# PANS.net
KiCad netlist of a schematic drawn in EAGLE
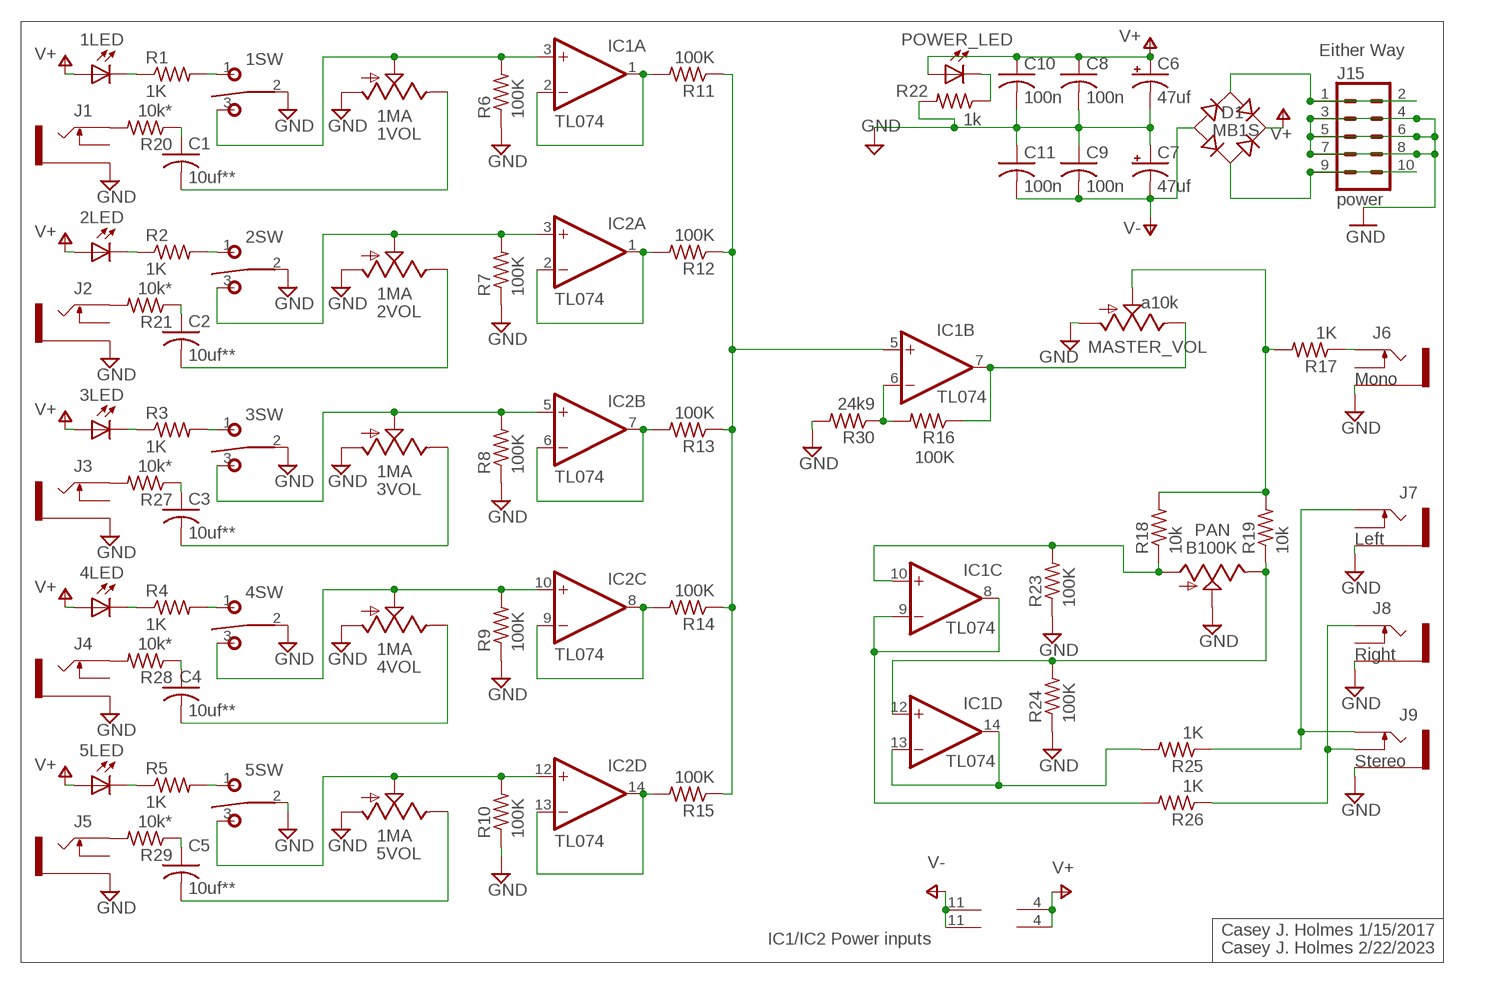
[diagram p0: schematic, sheet 1]

(export (version "E")
  (design (tool "Eeschema 10.0.6"))
  (components
    (comp (ref "1LED")
      (value "green")
      (footprint "eagle-import:LED5MM")
      (libsource (lib "eagle-import") (part "LED5MM"))
    )
    (comp (ref "1SW")
      (value "on/on")
      (footprint "eagle-import:M9040P")
      (libsource (lib "eagle-import") (part "T-80-T-SPDT-ON-OFF-ON"))
    )
    (comp (ref "1VOL")
      (value "1MA")
      (footprint "eagle-import:9MM_SNAP-IN_POT")
      (libsource (lib "eagle-import") (part "9MM_SNAP-IN_POT_"))
    )
    (comp (ref "2LED")
      (value "green")
      (footprint "eagle-import:LED5MM")
      (libsource (lib "eagle-import") (part "LED5MM"))
    )
    (comp (ref "2SW")
      (value "on/on")
      (footprint "eagle-import:M9040P")
      (libsource (lib "eagle-import") (part "T-80-T-SPDT-ON-OFF-ON"))
    )
    (comp (ref "2VOL")
      (value "1MA")
      (footprint "eagle-import:9MM_SNAP-IN_POT")
      (libsource (lib "eagle-import") (part "9MM_SNAP-IN_POT_"))
    )
    (comp (ref "3LED")
      (value "green")
      (footprint "eagle-import:LED5MM")
      (libsource (lib "eagle-import") (part "LED5MM"))
    )
    (comp (ref "3SW")
      (value "on/on")
      (footprint "eagle-import:M9040P")
      (libsource (lib "eagle-import") (part "T-80-T-SPDT-ON-OFF-ON"))
    )
    (comp (ref "3VOL")
      (value "1MA")
      (footprint "eagle-import:9MM_SNAP-IN_POT")
      (libsource (lib "eagle-import") (part "9MM_SNAP-IN_POT_"))
    )
    (comp (ref "4LED")
      (value "green")
      (footprint "eagle-import:LED5MM")
      (libsource (lib "eagle-import") (part "LED5MM"))
    )
    (comp (ref "4SW")
      (value "on/on")
      (footprint "eagle-import:M9040P")
      (libsource (lib "eagle-import") (part "T-80-T-SPDT-ON-OFF-ON"))
    )
    (comp (ref "4VOL")
      (value "1MA")
      (footprint "eagle-import:9MM_SNAP-IN_POT")
      (libsource (lib "eagle-import") (part "9MM_SNAP-IN_POT_"))
    )
    (comp (ref "5LED")
      (value "green")
      (footprint "eagle-import:LED5MM")
      (libsource (lib "eagle-import") (part "LED5MM"))
    )
    (comp (ref "5SW")
      (value "on/on")
      (footprint "eagle-import:M9040P")
      (libsource (lib "eagle-import") (part "T-80-T-SPDT-ON-OFF-ON"))
    )
    (comp (ref "5VOL")
      (value "1MA")
      (footprint "eagle-import:9MM_SNAP-IN_POT")
      (libsource (lib "eagle-import") (part "9MM_SNAP-IN_POT_"))
    )
    (comp (ref "C1")
      (value "10uf**")
      (footprint "eagle-import:C0805K")
      (libsource (lib "eagle-import") (part "C-USC0805K"))
    )
    (comp (ref "C2")
      (value "10uf**")
      (footprint "eagle-import:C0805K")
      (libsource (lib "eagle-import") (part "C-USC0805K"))
    )
    (comp (ref "C3")
      (value "10uf**")
      (footprint "eagle-import:C0805K")
      (libsource (lib "eagle-import") (part "C-USC0805K"))
    )
    (comp (ref "C4")
      (value "10uf**")
      (footprint "eagle-import:C0805K")
      (libsource (lib "eagle-import") (part "C-USC0805K"))
    )
    (comp (ref "C5")
      (value "10uf**")
      (footprint "eagle-import:C0805K")
      (libsource (lib "eagle-import") (part "C-USC0805K"))
    )
    (comp (ref "C6")
      (value "47uf")
      (footprint "eagle-import:PANASONIC_D")
      (libsource (lib "eagle-import") (part "CPOL-USD"))
    )
    (comp (ref "C7")
      (value "47uf")
      (footprint "eagle-import:PANASONIC_D")
      (libsource (lib "eagle-import") (part "CPOL-USD"))
    )
    (comp (ref "C8")
      (value "100n")
      (footprint "eagle-import:C0805")
      (libsource (lib "eagle-import") (part "resistor_C-USC0805"))
    )
    (comp (ref "C9")
      (value "100n")
      (footprint "eagle-import:C0805")
      (libsource (lib "eagle-import") (part "resistor_C-USC0805"))
    )
    (comp (ref "C10")
      (value "100n")
      (footprint "eagle-import:C0805")
      (libsource (lib "eagle-import") (part "resistor_C-USC0805"))
    )
    (comp (ref "C11")
      (value "100n")
      (footprint "eagle-import:C0805")
      (libsource (lib "eagle-import") (part "resistor_C-USC0805"))
    )
    (comp (ref "D1")
      (value "MB1S")
      (footprint "eagle-import:SOIC-4")
      (libsource (lib "eagle-import") (part "MBS1"))
    )
    (comp (ref "IC1")
      (value "TL074")
      (footprint "eagle-import:SO14")
      (libsource (lib "eagle-import") (part "TL074_SMD"))
    )
    (comp (ref "IC2")
      (value "TL074")
      (footprint "eagle-import:SO14")
      (libsource (lib "eagle-import") (part "TL074_SMD"))
    )
    (comp (ref "J1")
      (value "THONKICONNNEW")
      (footprint "eagle-import:WQP-PJ301M-12_JACK")
      (libsource (lib "eagle-import") (part "THONKICONNNEW"))
    )
    (comp (ref "J2")
      (value "THONKICONNNEW")
      (footprint "eagle-import:WQP-PJ301M-12_JACK")
      (libsource (lib "eagle-import") (part "THONKICONNNEW"))
    )
    (comp (ref "J3")
      (value "THONKICONNNEW")
      (footprint "eagle-import:WQP-PJ301M-12_JACK")
      (libsource (lib "eagle-import") (part "THONKICONNNEW"))
    )
    (comp (ref "J4")
      (value "THONKICONNNEW")
      (footprint "eagle-import:WQP-PJ301M-12_JACK")
      (libsource (lib "eagle-import") (part "THONKICONNNEW"))
    )
    (comp (ref "J5")
      (value "THONKICONNNEW")
      (footprint "eagle-import:WQP-PJ301M-12_JACK")
      (libsource (lib "eagle-import") (part "THONKICONNNEW"))
    )
    (comp (ref "J6")
      (value "THONKICONNNEW")
      (footprint "eagle-import:WQP-PJ301M-12_JACK")
      (libsource (lib "eagle-import") (part "THONKICONNNEW"))
    )
    (comp (ref "J7")
      (value "LEFT")
      (footprint "eagle-import:WQP-PJ301M-12_JACK")
      (libsource (lib "eagle-import") (part "THONKICONNNEW"))
    )
    (comp (ref "J8")
      (value "THONKICONNNEW")
      (footprint "eagle-import:WQP-PJ301M-12_JACK")
      (libsource (lib "eagle-import") (part "THONKICONNNEW"))
    )
    (comp (ref "J9")
      (value "Stereo")
      (footprint "eagle-import:WQP-PJ301M-12_JACK")
      (libsource (lib "eagle-import") (part "THONKICONNNEW"))
    )
    (comp (ref "J15")
      (value "power")
      (footprint "eagle-import:2X5")
      (libsource (lib "eagle-import") (part "CONN_05X2PTH"))
    )
    (comp (ref "MASTER_VOL")
      (value "a10k")
      (footprint "eagle-import:9MM_SNAP-IN_POT")
      (libsource (lib "eagle-import") (part "9MM_SNAP-IN_POT_"))
    )
    (comp (ref "PAN")
      (value "B100K")
      (footprint "eagle-import:9MM_SNAP-IN_POT")
      (libsource (lib "eagle-import") (part "9MM_SNAP-IN_POT_"))
    )
    (comp (ref "POWER_LED")
      (value "green")
      (footprint "eagle-import:LED5MM")
      (libsource (lib "eagle-import") (part "LED5MM"))
    )
    (comp (ref "R1")
      (value "1K")
      (footprint "eagle-import:M0805")
      (libsource (lib "eagle-import") (part "R-US_M0805"))
    )
    (comp (ref "R2")
      (value "1K")
      (footprint "eagle-import:M0805")
      (libsource (lib "eagle-import") (part "R-US_M0805"))
    )
    (comp (ref "R3")
      (value "1K")
      (footprint "eagle-import:M0805")
      (libsource (lib "eagle-import") (part "R-US_M0805"))
    )
    (comp (ref "R4")
      (value "1K")
      (footprint "eagle-import:M0805")
      (libsource (lib "eagle-import") (part "R-US_M0805"))
    )
    (comp (ref "R5")
      (value "1K")
      (footprint "eagle-import:M0805")
      (libsource (lib "eagle-import") (part "R-US_M0805"))
    )
    (comp (ref "R6")
      (value "100K")
      (footprint "eagle-import:M0805")
      (libsource (lib "eagle-import") (part "R-US_M0805"))
    )
    (comp (ref "R7")
      (value "100K")
      (footprint "eagle-import:M0805")
      (libsource (lib "eagle-import") (part "R-US_M0805"))
    )
    (comp (ref "R8")
      (value "100K")
      (footprint "eagle-import:M0805")
      (libsource (lib "eagle-import") (part "R-US_M0805"))
    )
    (comp (ref "R9")
      (value "100K")
      (footprint "eagle-import:M0805")
      (libsource (lib "eagle-import") (part "R-US_M0805"))
    )
    (comp (ref "R10")
      (value "100K")
      (footprint "eagle-import:M0805")
      (libsource (lib "eagle-import") (part "R-US_M0805"))
    )
    (comp (ref "R11")
      (value "100K")
      (footprint "eagle-import:M0805")
      (libsource (lib "eagle-import") (part "R-US_M0805"))
    )
    (comp (ref "R12")
      (value "100K")
      (footprint "eagle-import:M0805")
      (libsource (lib "eagle-import") (part "R-US_M0805"))
    )
    (comp (ref "R13")
      (value "100K")
      (footprint "eagle-import:M0805")
      (libsource (lib "eagle-import") (part "R-US_M0805"))
    )
    (comp (ref "R14")
      (value "100K")
      (footprint "eagle-import:M0805")
      (libsource (lib "eagle-import") (part "R-US_M0805"))
    )
    (comp (ref "R15")
      (value "100K")
      (footprint "eagle-import:M0805")
      (libsource (lib "eagle-import") (part "R-US_M0805"))
    )
    (comp (ref "R16")
      (value "100K")
      (footprint "eagle-import:M0805")
      (libsource (lib "eagle-import") (part "R-US_M0805"))
    )
    (comp (ref "R17")
      (value "1K")
      (footprint "eagle-import:M0805")
      (libsource (lib "eagle-import") (part "R-US_M0805"))
    )
    (comp (ref "R18")
      (value "10k")
      (footprint "eagle-import:M0805")
      (libsource (lib "eagle-import") (part "R-US_M0805"))
    )
    (comp (ref "R19")
      (value "10k")
      (footprint "eagle-import:M0805")
      (libsource (lib "eagle-import") (part "R-US_M0805"))
    )
    (comp (ref "R20")
      (value "10k*")
      (footprint "eagle-import:M0805")
      (libsource (lib "eagle-import") (part "R-US_M0805"))
    )
    (comp (ref "R21")
      (value "10k*")
      (footprint "eagle-import:M0805")
      (libsource (lib "eagle-import") (part "R-US_M0805"))
    )
    (comp (ref "R22")
      (value "1k")
      (footprint "eagle-import:M0805")
      (libsource (lib "eagle-import") (part "R-US_M0805"))
    )
    (comp (ref "R23")
      (value "100K")
      (footprint "eagle-import:M0805")
      (libsource (lib "eagle-import") (part "R-US_M0805"))
    )
    (comp (ref "R24")
      (value "100K")
      (footprint "eagle-import:M0805")
      (libsource (lib "eagle-import") (part "R-US_M0805"))
    )
    (comp (ref "R25")
      (value "1K")
      (footprint "eagle-import:M0805")
      (libsource (lib "eagle-import") (part "R-US_M0805"))
    )
    (comp (ref "R26")
      (value "1K")
      (footprint "eagle-import:M0805")
      (libsource (lib "eagle-import") (part "R-US_M0805"))
    )
    (comp (ref "R27")
      (value "10k*")
      (footprint "eagle-import:M0805")
      (libsource (lib "eagle-import") (part "R-US_M0805"))
    )
    (comp (ref "R28")
      (value "10k*")
      (footprint "eagle-import:M0805")
      (libsource (lib "eagle-import") (part "R-US_M0805"))
    )
    (comp (ref "R29")
      (value "10k*")
      (footprint "eagle-import:M0805")
      (libsource (lib "eagle-import") (part "R-US_M0805"))
    )
    (comp (ref "R30")
      (value "24k9")
      (footprint "eagle-import:M0805")
      (libsource (lib "eagle-import") (part "R-US_M0805"))
    )
  )
  (nets
    (net (code "1") (name "GND") (class "Default")
      (node (ref "1SW") (pin "2") (pinfunction "P_2") (pintype "passive"))
      (node (ref "1VOL") (pin "1") (pinfunction "A_1") (pintype "passive"))
      (node (ref "2SW") (pin "2") (pinfunction "P_2") (pintype "passive"))
      (node (ref "2VOL") (pin "1") (pinfunction "A_1") (pintype "passive"))
      (node (ref "3SW") (pin "2") (pinfunction "P_2") (pintype "passive"))
      (node (ref "3VOL") (pin "1") (pinfunction "A_1") (pintype "passive"))
      (node (ref "4SW") (pin "2") (pinfunction "P_2") (pintype "passive"))
      (node (ref "4VOL") (pin "1") (pinfunction "A_1") (pintype "passive"))
      (node (ref "5SW") (pin "2") (pinfunction "P_2") (pintype "passive"))
      (node (ref "5VOL") (pin "1") (pinfunction "A_1") (pintype "passive"))
      (node (ref "C10") (pin "2") (pinfunction "2_2") (pintype "passive"))
      (node (ref "C11") (pin "1") (pinfunction "1_1") (pintype "passive"))
      (node (ref "C6") (pin "-") (pinfunction "-_-") (pintype "passive"))
      (node (ref "C7") (pin "+") (pinfunction "+_+") (pintype "passive"))
      (node (ref "C8") (pin "2") (pinfunction "2_2") (pintype "passive"))
      (node (ref "C9") (pin "1") (pinfunction "1_1") (pintype "passive"))
      (node (ref "J1") (pin "P$3_SLEEVE") (pinfunction "SLEEVE_P$3_SLEEVE") (pintype "passive"))
      (node (ref "J15") (pin "3") (pinfunction "3_3") (pintype "passive"))
      (node (ref "J15") (pin "4") (pinfunction "4_4") (pintype "passive"))
      (node (ref "J15") (pin "5") (pinfunction "5_5") (pintype "passive"))
      (node (ref "J15") (pin "6") (pinfunction "6_6") (pintype "passive"))
      (node (ref "J15") (pin "7") (pinfunction "7_7") (pintype "passive"))
      (node (ref "J15") (pin "8") (pinfunction "8_8") (pintype "passive"))
      (node (ref "J2") (pin "P$3_SLEEVE") (pinfunction "SLEEVE_P$3_SLEEVE") (pintype "passive"))
      (node (ref "J3") (pin "P$3_SLEEVE") (pinfunction "SLEEVE_P$3_SLEEVE") (pintype "passive"))
      (node (ref "J4") (pin "P$3_SLEEVE") (pinfunction "SLEEVE_P$3_SLEEVE") (pintype "passive"))
      (node (ref "J5") (pin "P$3_SLEEVE") (pinfunction "SLEEVE_P$3_SLEEVE") (pintype "passive"))
      (node (ref "J6") (pin "P$3_SLEEVE") (pinfunction "SLEEVE_P$3_SLEEVE") (pintype "passive"))
      (node (ref "J7") (pin "P$3_SLEEVE") (pinfunction "SLEEVE_P$3_SLEEVE") (pintype "passive"))
      (node (ref "J8") (pin "P$3_SLEEVE") (pinfunction "SLEEVE_P$3_SLEEVE") (pintype "passive"))
      (node (ref "J9") (pin "P$3_SLEEVE") (pinfunction "SLEEVE_P$3_SLEEVE") (pintype "passive"))
      (node (ref "MASTER_VOL") (pin "1") (pinfunction "A_1") (pintype "passive"))
      (node (ref "PAN") (pin "2") (pinfunction "S_2") (pintype "passive"))
      (node (ref "R10") (pin "1") (pinfunction "1_1") (pintype "passive"))
      (node (ref "R22") (pin "2") (pinfunction "2_2") (pintype "passive"))
      (node (ref "R23") (pin "1") (pinfunction "1_1") (pintype "passive"))
      (node (ref "R24") (pin "1") (pinfunction "1_1") (pintype "passive"))
      (node (ref "R30") (pin "2") (pinfunction "2_2") (pintype "passive"))
      (node (ref "R6") (pin "1") (pinfunction "1_1") (pintype "passive"))
      (node (ref "R7") (pin "1") (pinfunction "1_1") (pintype "passive"))
      (node (ref "R8") (pin "1") (pinfunction "1_1") (pintype "passive"))
      (node (ref "R9") (pin "1") (pinfunction "1_1") (pintype "passive"))
    )
    (net (code "2") (name "Net-(1LED-C)") (class "Default")
      (node (ref "1LED") (pin "K") (pinfunction "C_K") (pintype "passive"))
      (node (ref "R1") (pin "1") (pinfunction "1_1") (pintype "passive"))
    )
    (net (code "3") (name "Net-(1SW-O)") (class "Default")
      (node (ref "1SW") (pin "1") (pinfunction "O_1") (pintype "passive"))
      (node (ref "R1") (pin "2") (pinfunction "2_2") (pintype "passive"))
    )
    (net (code "4") (name "Net-(1SW-S)") (class "Default")
      (node (ref "1SW") (pin "3") (pinfunction "S_3") (pintype "passive"))
      (node (ref "1VOL") (pin "2") (pinfunction "S_2") (pintype "passive"))
      (node (ref "IC1") (pin "3") (pinfunction "+IN_3") (pintype "input"))
      (node (ref "R6") (pin "2") (pinfunction "2_2") (pintype "passive"))
    )
    (net (code "5") (name "Net-(1VOL-E)") (class "Default")
      (node (ref "1VOL") (pin "3") (pinfunction "E_3") (pintype "passive"))
      (node (ref "C1") (pin "2") (pinfunction "2_2") (pintype "passive"))
    )
    (net (code "6") (name "Net-(2LED-C)") (class "Default")
      (node (ref "2LED") (pin "K") (pinfunction "C_K") (pintype "passive"))
      (node (ref "R2") (pin "1") (pinfunction "1_1") (pintype "passive"))
    )
    (net (code "7") (name "Net-(2SW-O)") (class "Default")
      (node (ref "2SW") (pin "1") (pinfunction "O_1") (pintype "passive"))
      (node (ref "R2") (pin "2") (pinfunction "2_2") (pintype "passive"))
    )
    (net (code "8") (name "Net-(2SW-S)") (class "Default")
      (node (ref "2SW") (pin "3") (pinfunction "S_3") (pintype "passive"))
      (node (ref "2VOL") (pin "2") (pinfunction "S_2") (pintype "passive"))
      (node (ref "IC2") (pin "3") (pinfunction "+IN_3") (pintype "input"))
      (node (ref "R7") (pin "2") (pinfunction "2_2") (pintype "passive"))
    )
    (net (code "9") (name "Net-(2VOL-E)") (class "Default")
      (node (ref "2VOL") (pin "3") (pinfunction "E_3") (pintype "passive"))
      (node (ref "C2") (pin "2") (pinfunction "2_2") (pintype "passive"))
    )
    (net (code "10") (name "Net-(3LED-C)") (class "Default")
      (node (ref "3LED") (pin "K") (pinfunction "C_K") (pintype "passive"))
      (node (ref "R3") (pin "1") (pinfunction "1_1") (pintype "passive"))
    )
    (net (code "11") (name "Net-(3SW-O)") (class "Default")
      (node (ref "3SW") (pin "1") (pinfunction "O_1") (pintype "passive"))
      (node (ref "R3") (pin "2") (pinfunction "2_2") (pintype "passive"))
    )
    (net (code "12") (name "Net-(3SW-S)") (class "Default")
      (node (ref "3SW") (pin "3") (pinfunction "S_3") (pintype "passive"))
      (node (ref "3VOL") (pin "2") (pinfunction "S_2") (pintype "passive"))
      (node (ref "IC2") (pin "5") (pinfunction "+IN_5") (pintype "input"))
      (node (ref "R8") (pin "2") (pinfunction "2_2") (pintype "passive"))
    )
    (net (code "13") (name "Net-(3VOL-E)") (class "Default")
      (node (ref "3VOL") (pin "3") (pinfunction "E_3") (pintype "passive"))
      (node (ref "C3") (pin "2") (pinfunction "2_2") (pintype "passive"))
    )
    (net (code "14") (name "Net-(4LED-C)") (class "Default")
      (node (ref "4LED") (pin "K") (pinfunction "C_K") (pintype "passive"))
      (node (ref "R4") (pin "1") (pinfunction "1_1") (pintype "passive"))
    )
    (net (code "15") (name "Net-(4SW-O)") (class "Default")
      (node (ref "4SW") (pin "1") (pinfunction "O_1") (pintype "passive"))
      (node (ref "R4") (pin "2") (pinfunction "2_2") (pintype "passive"))
    )
    (net (code "16") (name "Net-(4SW-S)") (class "Default")
      (node (ref "4SW") (pin "3") (pinfunction "S_3") (pintype "passive"))
      (node (ref "4VOL") (pin "2") (pinfunction "S_2") (pintype "passive"))
      (node (ref "IC2") (pin "10") (pinfunction "+IN_10") (pintype "input"))
      (node (ref "R9") (pin "2") (pinfunction "2_2") (pintype "passive"))
    )
    (net (code "17") (name "Net-(4VOL-E)") (class "Default")
      (node (ref "4VOL") (pin "3") (pinfunction "E_3") (pintype "passive"))
      (node (ref "C4") (pin "2") (pinfunction "2_2") (pintype "passive"))
    )
    (net (code "18") (name "Net-(5LED-C)") (class "Default")
      (node (ref "5LED") (pin "K") (pinfunction "C_K") (pintype "passive"))
      (node (ref "R5") (pin "1") (pinfunction "1_1") (pintype "passive"))
    )
    (net (code "19") (name "Net-(5SW-O)") (class "Default")
      (node (ref "5SW") (pin "1") (pinfunction "O_1") (pintype "passive"))
      (node (ref "R5") (pin "2") (pinfunction "2_2") (pintype "passive"))
    )
    (net (code "20") (name "Net-(5SW-S)") (class "Default")
      (node (ref "5SW") (pin "3") (pinfunction "S_3") (pintype "passive"))
      (node (ref "5VOL") (pin "2") (pinfunction "S_2") (pintype "passive"))
      (node (ref "IC2") (pin "12") (pinfunction "+IN_12") (pintype "input"))
      (node (ref "R10") (pin "2") (pinfunction "2_2") (pintype "passive"))
    )
    (net (code "21") (name "Net-(5VOL-E)") (class "Default")
      (node (ref "5VOL") (pin "3") (pinfunction "E_3") (pintype "passive"))
      (node (ref "C5") (pin "2") (pinfunction "2_2") (pintype "passive"))
    )
    (net (code "22") (name "Net-(C1-Pad1)") (class "Default")
      (node (ref "C1") (pin "1") (pinfunction "1_1") (pintype "passive"))
      (node (ref "R20") (pin "1") (pinfunction "1_1") (pintype "passive"))
    )
    (net (code "23") (name "Net-(C2-Pad1)") (class "Default")
      (node (ref "C2") (pin "1") (pinfunction "1_1") (pintype "passive"))
      (node (ref "R21") (pin "1") (pinfunction "1_1") (pintype "passive"))
    )
    (net (code "24") (name "Net-(C3-Pad1)") (class "Default")
      (node (ref "C3") (pin "1") (pinfunction "1_1") (pintype "passive"))
      (node (ref "R27") (pin "1") (pinfunction "1_1") (pintype "passive"))
    )
    (net (code "25") (name "Net-(C4-Pad1)") (class "Default")
      (node (ref "C4") (pin "1") (pinfunction "1_1") (pintype "passive"))
      (node (ref "R28") (pin "1") (pinfunction "1_1") (pintype "passive"))
    )
    (net (code "26") (name "Net-(C5-Pad1)") (class "Default")
      (node (ref "C5") (pin "1") (pinfunction "1_1") (pintype "passive"))
      (node (ref "R29") (pin "1") (pinfunction "1_1") (pintype "passive"))
    )
    (net (code "27") (name "Net-(D1-AC1)") (class "Default")
      (node (ref "D1") (pin "~1") (pinfunction "AC1_~1") (pintype "passive"))
      (node (ref "J15") (pin "1") (pinfunction "1_1") (pintype "passive"))
      (node (ref "J15") (pin "2") (pinfunction "2_2") (pintype "passive"))
    )
    (net (code "28") (name "Net-(D1-AC2)") (class "Default")
      (node (ref "D1") (pin "~2") (pinfunction "AC2_~2") (pintype "passive"))
      (node (ref "J15") (pin "10") (pinfunction "10_10") (pintype "passive"))
      (node (ref "J15") (pin "9") (pinfunction "9_9") (pintype "passive"))
    )
    (net (code "29") (name "Net-(IC1A--IN)") (class "Default")
      (node (ref "IC1") (pin "1") (pinfunction "OUT_1") (pintype "output"))
      (node (ref "IC1") (pin "2") (pinfunction "-IN_2") (pintype "input"))
      (node (ref "R11") (pin "2") (pinfunction "2_2") (pintype "passive"))
    )
    (net (code "30") (name "Net-(IC1B-+IN)") (class "Default")
      (node (ref "IC1") (pin "5") (pinfunction "+IN_5") (pintype "input"))
      (node (ref "R11") (pin "1") (pinfunction "1_1") (pintype "passive"))
      (node (ref "R12") (pin "1") (pinfunction "1_1") (pintype "passive"))
      (node (ref "R13") (pin "1") (pinfunction "1_1") (pintype "passive"))
      (node (ref "R14") (pin "1") (pinfunction "1_1") (pintype "passive"))
      (node (ref "R15") (pin "1") (pinfunction "1_1") (pintype "passive"))
    )
    (net (code "31") (name "Net-(IC1B--IN)") (class "Default")
      (node (ref "IC1") (pin "6") (pinfunction "-IN_6") (pintype "input"))
      (node (ref "R16") (pin "2") (pinfunction "2_2") (pintype "passive"))
      (node (ref "R30") (pin "1") (pinfunction "1_1") (pintype "passive"))
    )
    (net (code "32") (name "Net-(IC1B-OUT)") (class "Default")
      (node (ref "IC1") (pin "7") (pinfunction "OUT_7") (pintype "output"))
      (node (ref "MASTER_VOL") (pin "3") (pinfunction "E_3") (pintype "passive"))
      (node (ref "R16") (pin "1") (pinfunction "1_1") (pintype "passive"))
    )
    (net (code "33") (name "Net-(IC1C-+IN)") (class "Default")
      (node (ref "IC1") (pin "10") (pinfunction "+IN_10") (pintype "input"))
      (node (ref "PAN") (pin "1") (pinfunction "A_1") (pintype "passive"))
      (node (ref "R18") (pin "1") (pinfunction "1_1") (pintype "passive"))
      (node (ref "R23") (pin "2") (pinfunction "2_2") (pintype "passive"))
    )
    (net (code "34") (name "Net-(IC1C--IN)") (class "Default")
      (node (ref "IC1") (pin "8") (pinfunction "OUT_8") (pintype "output"))
      (node (ref "IC1") (pin "9") (pinfunction "-IN_9") (pintype "input"))
      (node (ref "R26") (pin "2") (pinfunction "2_2") (pintype "passive"))
    )
    (net (code "35") (name "Net-(IC1D-+IN)") (class "Default")
      (node (ref "IC1") (pin "12") (pinfunction "+IN_12") (pintype "input"))
      (node (ref "PAN") (pin "3") (pinfunction "E_3") (pintype "passive"))
      (node (ref "R19") (pin "1") (pinfunction "1_1") (pintype "passive"))
      (node (ref "R24") (pin "2") (pinfunction "2_2") (pintype "passive"))
    )
    (net (code "36") (name "Net-(IC1D--IN)") (class "Default")
      (node (ref "IC1") (pin "13") (pinfunction "-IN_13") (pintype "input"))
      (node (ref "IC1") (pin "14") (pinfunction "OUT_14") (pintype "output"))
      (node (ref "R25") (pin "2") (pinfunction "2_2") (pintype "passive"))
    )
    (net (code "37") (name "Net-(IC2A--IN)") (class "Default")
      (node (ref "IC2") (pin "1") (pinfunction "OUT_1") (pintype "output"))
      (node (ref "IC2") (pin "2") (pinfunction "-IN_2") (pintype "input"))
      (node (ref "R12") (pin "2") (pinfunction "2_2") (pintype "passive"))
    )
    (net (code "38") (name "Net-(IC2B--IN)") (class "Default")
      (node (ref "IC2") (pin "6") (pinfunction "-IN_6") (pintype "input"))
      (node (ref "IC2") (pin "7") (pinfunction "OUT_7") (pintype "output"))
      (node (ref "R13") (pin "2") (pinfunction "2_2") (pintype "passive"))
    )
    (net (code "39") (name "Net-(IC2C--IN)") (class "Default")
      (node (ref "IC2") (pin "8") (pinfunction "OUT_8") (pintype "output"))
      (node (ref "IC2") (pin "9") (pinfunction "-IN_9") (pintype "input"))
      (node (ref "R14") (pin "2") (pinfunction "2_2") (pintype "passive"))
    )
    (net (code "40") (name "Net-(IC2D--IN)") (class "Default")
      (node (ref "IC2") (pin "13") (pinfunction "-IN_13") (pintype "input"))
      (node (ref "IC2") (pin "14") (pinfunction "OUT_14") (pintype "output"))
      (node (ref "R15") (pin "2") (pinfunction "2_2") (pintype "passive"))
    )
    (net (code "41") (name "Net-(J1-TIP)") (class "Default")
      (node (ref "J1") (pin "P$1_TIP") (pinfunction "TIP_P$1_TIP") (pintype "passive"))
      (node (ref "R20") (pin "2") (pinfunction "2_2") (pintype "passive"))
    )
    (net (code "42") (name "Net-(J2-TIP)") (class "Default")
      (node (ref "J2") (pin "P$1_TIP") (pinfunction "TIP_P$1_TIP") (pintype "passive"))
      (node (ref "R21") (pin "2") (pinfunction "2_2") (pintype "passive"))
    )
    (net (code "43") (name "Net-(J3-TIP)") (class "Default")
      (node (ref "J3") (pin "P$1_TIP") (pinfunction "TIP_P$1_TIP") (pintype "passive"))
      (node (ref "R27") (pin "2") (pinfunction "2_2") (pintype "passive"))
    )
    (net (code "44") (name "Net-(J4-TIP)") (class "Default")
      (node (ref "J4") (pin "P$1_TIP") (pinfunction "TIP_P$1_TIP") (pintype "passive"))
      (node (ref "R28") (pin "2") (pinfunction "2_2") (pintype "passive"))
    )
    (net (code "45") (name "Net-(J5-TIP)") (class "Default")
      (node (ref "J5") (pin "P$1_TIP") (pinfunction "TIP_P$1_TIP") (pintype "passive"))
      (node (ref "R29") (pin "2") (pinfunction "2_2") (pintype "passive"))
    )
    (net (code "46") (name "Net-(J6-TIP)") (class "Default")
      (node (ref "J6") (pin "P$1_TIP") (pinfunction "TIP_P$1_TIP") (pintype "passive"))
      (node (ref "R17") (pin "1") (pinfunction "1_1") (pintype "passive"))
    )
    (net (code "47") (name "Net-(J7-TIP)") (class "Default")
      (node (ref "J7") (pin "P$1_TIP") (pinfunction "TIP_P$1_TIP") (pintype "passive"))
      (node (ref "J9") (pin "P$1_TIP") (pinfunction "TIP_P$1_TIP") (pintype "passive"))
      (node (ref "R25") (pin "1") (pinfunction "1_1") (pintype "passive"))
    )
    (net (code "48") (name "Net-(J8-TIP)") (class "Default")
      (node (ref "J8") (pin "P$1_TIP") (pinfunction "TIP_P$1_TIP") (pintype "passive"))
      (node (ref "J9") (pin "P$2_SWITCH") (pinfunction "SWITCH_P$2_SWITCH") (pintype "passive"))
      (node (ref "R26") (pin "1") (pinfunction "1_1") (pintype "passive"))
    )
    (net (code "49") (name "Net-(MASTER_VOL-S)") (class "Default")
      (node (ref "MASTER_VOL") (pin "2") (pinfunction "S_2") (pintype "passive"))
      (node (ref "R17") (pin "2") (pinfunction "2_2") (pintype "passive"))
      (node (ref "R18") (pin "2") (pinfunction "2_2") (pintype "passive"))
      (node (ref "R19") (pin "2") (pinfunction "2_2") (pintype "passive"))
    )
    (net (code "50") (name "Net-(POWER_LED-C)") (class "Default")
      (node (ref "POWER_LED") (pin "K") (pinfunction "C_K") (pintype "passive"))
      (node (ref "R22") (pin "1") (pinfunction "1_1") (pintype "passive"))
    )
    (net (code "51") (name "V+") (class "Default")
      (node (ref "1LED") (pin "A") (pinfunction "A_A") (pintype "passive"))
      (node (ref "2LED") (pin "A") (pinfunction "A_A") (pintype "passive"))
      (node (ref "3LED") (pin "A") (pinfunction "A_A") (pintype "passive"))
      (node (ref "4LED") (pin "A") (pinfunction "A_A") (pintype "passive"))
      (node (ref "5LED") (pin "A") (pinfunction "A_A") (pintype "passive"))
      (node (ref "C10") (pin "1") (pinfunction "1_1") (pintype "passive"))
      (node (ref "C6") (pin "+") (pinfunction "+_+") (pintype "passive"))
      (node (ref "C8") (pin "1") (pinfunction "1_1") (pintype "passive"))
      (node (ref "D1") (pin "+") (pinfunction "+_+") (pintype "passive"))
      (node (ref "IC1") (pin "4") (pinfunction "V+_4") (pintype "power_in"))
      (node (ref "IC2") (pin "4") (pinfunction "V+_4") (pintype "power_in"))
      (node (ref "POWER_LED") (pin "A") (pinfunction "A_A") (pintype "passive"))
    )
    (net (code "52") (name "V-") (class "Default")
      (node (ref "C11") (pin "2") (pinfunction "2_2") (pintype "passive"))
      (node (ref "C7") (pin "-") (pinfunction "-_-") (pintype "passive"))
      (node (ref "C9") (pin "2") (pinfunction "2_2") (pintype "passive"))
      (node (ref "D1") (pin "-") (pinfunction "-_-") (pintype "passive"))
      (node (ref "IC1") (pin "11") (pinfunction "V-_11") (pintype "power_in"))
      (node (ref "IC2") (pin "11") (pinfunction "V-_11") (pintype "power_in"))
    )
    (net (code "53") (name "unconnected-(J1-SWITCH-PadP$2_SWITCH)") (class "Default")
      (node (ref "J1") (pin "P$2_SWITCH") (pinfunction "SWITCH_P$2_SWITCH") (pintype "passive"))
    )
    (net (code "54") (name "unconnected-(J2-SWITCH-PadP$2_SWITCH)") (class "Default")
      (node (ref "J2") (pin "P$2_SWITCH") (pinfunction "SWITCH_P$2_SWITCH") (pintype "passive"))
    )
    (net (code "55") (name "unconnected-(J3-SWITCH-PadP$2_SWITCH)") (class "Default")
      (node (ref "J3") (pin "P$2_SWITCH") (pinfunction "SWITCH_P$2_SWITCH") (pintype "passive"))
    )
    (net (code "56") (name "unconnected-(J4-SWITCH-PadP$2_SWITCH)") (class "Default")
      (node (ref "J4") (pin "P$2_SWITCH") (pinfunction "SWITCH_P$2_SWITCH") (pintype "passive"))
    )
    (net (code "57") (name "unconnected-(J5-SWITCH-PadP$2_SWITCH)") (class "Default")
      (node (ref "J5") (pin "P$2_SWITCH") (pinfunction "SWITCH_P$2_SWITCH") (pintype "passive"))
    )
    (net (code "58") (name "unconnected-(J6-SWITCH-PadP$2_SWITCH)") (class "Default")
      (node (ref "J6") (pin "P$2_SWITCH") (pinfunction "SWITCH_P$2_SWITCH") (pintype "passive"))
    )
    (net (code "59") (name "unconnected-(J7-SWITCH-PadP$2_SWITCH)") (class "Default")
      (node (ref "J7") (pin "P$2_SWITCH") (pinfunction "SWITCH_P$2_SWITCH") (pintype "passive"))
    )
    (net (code "60") (name "unconnected-(J8-SWITCH-PadP$2_SWITCH)") (class "Default")
      (node (ref "J8") (pin "P$2_SWITCH") (pinfunction "SWITCH_P$2_SWITCH") (pintype "passive"))
    )
  )
)
